# 04_LCD.net
KiCad netlist of a schematic drawn in Altium Designer
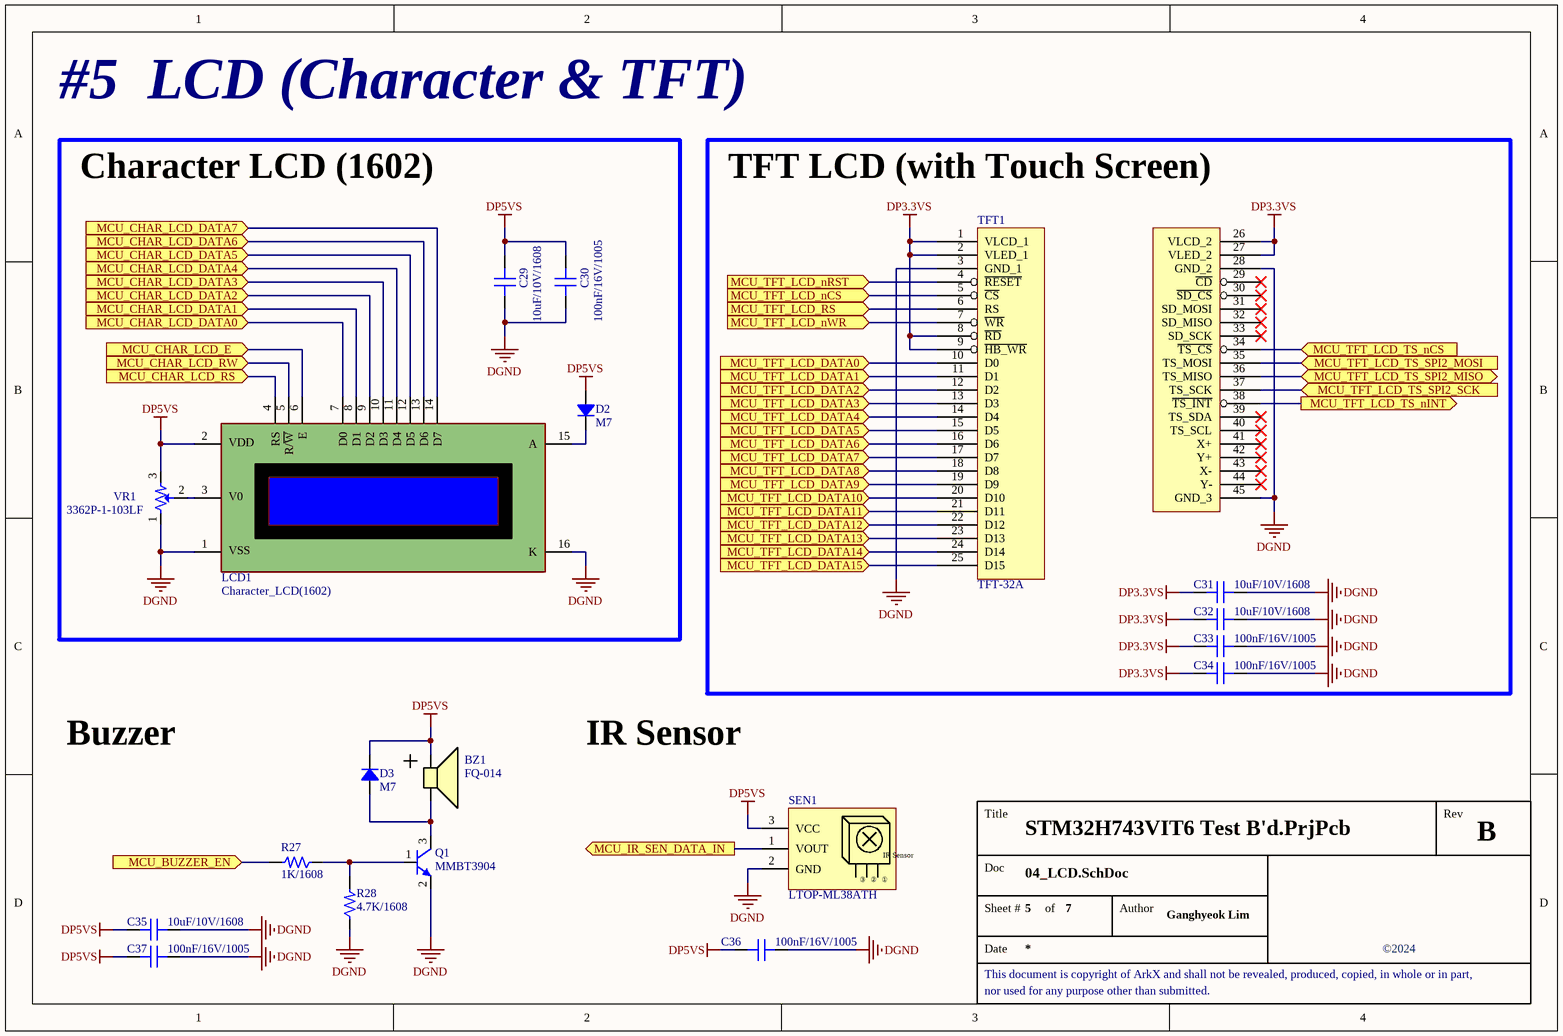
[diagram p0: 04_LCD.SchDoc]

(export (version "E")
  (design (tool "Eeschema 10.0.6"))
  (components
    (comp (ref "BZ1")
      (value "FQ-014")
      (footprint "BUZ FQ-013")
      (description "Magnetic Active Buzzer / Rated Voltage: 5V / Size: 9x5.5mm")
      (libsource (lib "Arkx") (part "BZ_FQ-014"))
    )
    (comp (ref "C29")
      (value "10uF/10V/1608")
      (footprint "CAP 1608 (0603_INCH)")
      (description "Ceramic CAP_10uF/10V/1608")
      (fields (field (name "LCSC PART #") "C19702"))
      (libsource (lib "Arkx") (part "CAP_10uF/10V/1608"))
    )
    (comp (ref "C30")
      (value "100nF/16V/1005")
      (footprint "CAP 1005 (0402_INCH)")
      (description "Ceramic CAP_100nF/16V/1005")
      (fields (field (name "LCSC PART #") "C1525"))
      (libsource (lib "Arkx") (part "CAP_100nF/16V/1005"))
    )
    (comp (ref "C31")
      (value "10uF/10V/1608")
      (footprint "CAP 1608 (0603_INCH)")
      (description "Ceramic CAP_10uF/10V/1608")
      (fields (field (name "LCSC PART #") "C19702"))
      (libsource (lib "Arkx") (part "CAP_10uF/10V/1608"))
    )
    (comp (ref "C32")
      (value "10uF/10V/1608")
      (footprint "CAP 1608 (0603_INCH)")
      (description "Ceramic CAP_10uF/10V/1608")
      (fields (field (name "LCSC PART #") "C19702"))
      (libsource (lib "Arkx") (part "CAP_10uF/10V/1608"))
    )
    (comp (ref "C33")
      (value "100nF/16V/1005")
      (footprint "CAP 1005 (0402_INCH)")
      (description "Ceramic CAP_100nF/16V/1005")
      (fields (field (name "LCSC PART #") "C1525"))
      (libsource (lib "Arkx") (part "CAP_100nF/16V/1005"))
    )
    (comp (ref "C34")
      (value "100nF/16V/1005")
      (footprint "CAP 1005 (0402_INCH)")
      (description "Ceramic CAP_100nF/16V/1005")
      (fields (field (name "LCSC PART #") "C1525"))
      (libsource (lib "Arkx") (part "CAP_100nF/16V/1005"))
    )
    (comp (ref "C35")
      (value "10uF/10V/1608")
      (footprint "CAP 1608 (0603_INCH)")
      (description "Ceramic CAP_10uF/10V/1608")
      (fields (field (name "LCSC PART #") "C19702"))
      (libsource (lib "Arkx") (part "CAP_10uF/10V/1608"))
    )
    (comp (ref "C36")
      (value "100nF/16V/1005")
      (footprint "CAP 1005 (0402_INCH)")
      (description "Ceramic CAP_100nF/16V/1005")
      (fields (field (name "LCSC PART #") "C1525"))
      (libsource (lib "Arkx") (part "CAP_100nF/16V/1005"))
    )
    (comp (ref "C37")
      (value "100nF/16V/1005")
      (footprint "CAP 1005 (0402_INCH)")
      (description "Ceramic CAP_100nF/16V/1005")
      (fields (field (name "LCSC PART #") "C1525"))
      (libsource (lib "Arkx") (part "CAP_100nF/16V/1005"))
    )
    (comp (ref "D2")
      (value "M7")
      (footprint "DIO DO-214AC (SMA)")
      (description "1A 5uA@1kV 1kV 1.1V@1A SMA(DO-214AC)  Diodes - General Purpose ROHS")
      (fields (field (name "LCSC PART #") "C95872"))
      (libsource (lib "Arkx") (part "DIO_M7"))
    )
    (comp (ref "D3")
      (value "M7")
      (footprint "DIO DO-214AC (SMA)")
      (description "1A 5uA@1kV 1kV 1.1V@1A SMA(DO-214AC)  Diodes - General Purpose ROHS")
      (fields (field (name "LCSC PART #") "C95872"))
      (libsource (lib "Arkx") (part "DIO_M7"))
    )
    (comp (ref "LCD1")
      (value "Character_LCD(1602)")
      (footprint "LCD_CHARACTOR-1602")
      (libsource (lib "Arkx") (part "LCD_Character-1602"))
    )
    (comp (ref "Q1")
      (value "MMBT3904")
      (footprint "SOT 23-3 (DIODES INCORPORATED)")
      (fields (field (name "LCSC PART #") "C20526"))
      (libsource (lib "Arkx") (part "BJT_NPN_MMBT3904"))
    )
    (comp (ref "R27")
      (value "1K/1608")
      (footprint "RES 1608 (0603_inch)")
      (description "RES_1K/1608/0.1W")
      (fields (field (name "LCSC PART #") "C21190"))
      (libsource (lib "Arkx") (part "RES_1K/1608/0.1W"))
    )
    (comp (ref "R28")
      (value "4.7K/1608")
      (footprint "RES 1608 (0603_inch)")
      (description "RES_4.7K/1608/0.1W")
      (fields (field (name "LCSC PART #") "C23162"))
      (libsource (lib "Arkx") (part "RES_4.7K/1608/0.1W"))
    )
    (comp (ref "SEN1")
      (value "LTOP-ML38ATH")
      (footprint "SEN_IR-LTOP-ML38ATH")
      (libsource (lib "Arkx") (part "SEN_IR_LTOP-ML38ATH"))
    )
    (comp (ref "TFT1")
      (value "TFT-32A")
      (footprint "LCD_TFT-32A")
      (libsource (lib "Arkx") (part "LCD_TFT-32A"))
    )
    (comp (ref "VR1")
      (value "3362P-1-103LF")
      (footprint "VR_3362P-1-103LF")
      (description "±10% ±100ppm/℃ 10kΩ Plugin  Variable Resistors/Potentiometers ROHS")
      (fields (field (name "LCSC PART #") "C58159"))
      (libsource (lib "Arkx") (part "VR_3362P-1-103LF"))
    )
  )
  (nets
    (net (code "1") (name "/MCU_BUZZER_EN") (class "Default")
      (node (ref "R27") (pin "2") (pinfunction "2_2") (pintype "passive"))
    )
    (net (code "2") (name "/MCU_CHAR_LCD_DATA0") (class "Default")
      (node (ref "LCD1") (pin "7") (pinfunction "D0_7") (pintype "passive"))
    )
    (net (code "3") (name "/MCU_CHAR_LCD_DATA1") (class "Default")
      (node (ref "LCD1") (pin "8") (pinfunction "D1_8") (pintype "passive"))
    )
    (net (code "4") (name "/MCU_CHAR_LCD_DATA2") (class "Default")
      (node (ref "LCD1") (pin "9") (pinfunction "D2_9") (pintype "passive"))
    )
    (net (code "5") (name "/MCU_CHAR_LCD_DATA3") (class "Default")
      (node (ref "LCD1") (pin "10") (pinfunction "D3_10") (pintype "passive"))
    )
    (net (code "6") (name "/MCU_CHAR_LCD_DATA4") (class "Default")
      (node (ref "LCD1") (pin "11") (pinfunction "D4_11") (pintype "passive"))
    )
    (net (code "7") (name "/MCU_CHAR_LCD_DATA5") (class "Default")
      (node (ref "LCD1") (pin "12") (pinfunction "D5_12") (pintype "passive"))
    )
    (net (code "8") (name "/MCU_CHAR_LCD_DATA6") (class "Default")
      (node (ref "LCD1") (pin "13") (pinfunction "D6_13") (pintype "passive"))
    )
    (net (code "9") (name "/MCU_CHAR_LCD_DATA7") (class "Default")
      (node (ref "LCD1") (pin "14") (pinfunction "D7_14") (pintype "passive"))
    )
    (net (code "10") (name "/MCU_CHAR_LCD_E") (class "Default")
      (node (ref "LCD1") (pin "6") (pinfunction "E_6") (pintype "passive"))
    )
    (net (code "11") (name "/MCU_CHAR_LCD_RS") (class "Default")
      (node (ref "LCD1") (pin "4") (pinfunction "RS_4") (pintype "passive"))
    )
    (net (code "12") (name "/MCU_CHAR_LCD_RW") (class "Default")
      (node (ref "LCD1") (pin "5") (pinfunction "R/~{W}_5") (pintype "passive"))
    )
    (net (code "13") (name "/MCU_IR_SEN_DATA_IN") (class "Default")
      (node (ref "SEN1") (pin "1") (pinfunction "VOUT_1") (pintype "passive"))
    )
    (net (code "14") (name "/MCU_TFT_LCD_DATA0") (class "Default")
      (node (ref "TFT1") (pin "10") (pinfunction "D0_10") (pintype "passive"))
    )
    (net (code "15") (name "/MCU_TFT_LCD_DATA1") (class "Default")
      (node (ref "TFT1") (pin "11") (pinfunction "D1_11") (pintype "passive"))
    )
    (net (code "16") (name "/MCU_TFT_LCD_DATA2") (class "Default")
      (node (ref "TFT1") (pin "12") (pinfunction "D2_12") (pintype "passive"))
    )
    (net (code "17") (name "/MCU_TFT_LCD_DATA3") (class "Default")
      (node (ref "TFT1") (pin "13") (pinfunction "D3_13") (pintype "passive"))
    )
    (net (code "18") (name "/MCU_TFT_LCD_DATA4") (class "Default")
      (node (ref "TFT1") (pin "14") (pinfunction "D4_14") (pintype "passive"))
    )
    (net (code "19") (name "/MCU_TFT_LCD_DATA5") (class "Default")
      (node (ref "TFT1") (pin "15") (pinfunction "D5_15") (pintype "passive"))
    )
    (net (code "20") (name "/MCU_TFT_LCD_DATA6") (class "Default")
      (node (ref "TFT1") (pin "16") (pinfunction "D6_16") (pintype "passive"))
    )
    (net (code "21") (name "/MCU_TFT_LCD_DATA7") (class "Default")
      (node (ref "TFT1") (pin "17") (pinfunction "D7_17") (pintype "passive"))
    )
    (net (code "22") (name "/MCU_TFT_LCD_DATA8") (class "Default")
      (node (ref "TFT1") (pin "18") (pinfunction "D8_18") (pintype "passive"))
    )
    (net (code "23") (name "/MCU_TFT_LCD_DATA9") (class "Default")
      (node (ref "TFT1") (pin "19") (pinfunction "D9_19") (pintype "passive"))
    )
    (net (code "24") (name "/MCU_TFT_LCD_DATA10") (class "Default")
      (node (ref "TFT1") (pin "20") (pinfunction "D10_20") (pintype "passive"))
    )
    (net (code "25") (name "/MCU_TFT_LCD_DATA11") (class "Default")
      (node (ref "TFT1") (pin "21") (pinfunction "D11_21") (pintype "passive"))
    )
    (net (code "26") (name "/MCU_TFT_LCD_DATA12") (class "Default")
      (node (ref "TFT1") (pin "22") (pinfunction "D12_22") (pintype "passive"))
    )
    (net (code "27") (name "/MCU_TFT_LCD_DATA13") (class "Default")
      (node (ref "TFT1") (pin "23") (pinfunction "D13_23") (pintype "passive"))
    )
    (net (code "28") (name "/MCU_TFT_LCD_DATA14") (class "Default")
      (node (ref "TFT1") (pin "24") (pinfunction "D14_24") (pintype "passive"))
    )
    (net (code "29") (name "/MCU_TFT_LCD_DATA15") (class "Default")
      (node (ref "TFT1") (pin "25") (pinfunction "D15_25") (pintype "passive"))
    )
    (net (code "30") (name "/MCU_TFT_LCD_RS") (class "Default")
      (node (ref "TFT1") (pin "6") (pinfunction "RS_6") (pintype "passive"))
    )
    (net (code "31") (name "/MCU_TFT_LCD_TS_SPI2_MISO") (class "Default")
      (node (ref "TFT1") (pin "36") (pinfunction "TS_MISO_36") (pintype "passive"))
    )
    (net (code "32") (name "/MCU_TFT_LCD_TS_SPI2_MOSI") (class "Default")
      (node (ref "TFT1") (pin "35") (pinfunction "TS_MOSI_35") (pintype "passive"))
    )
    (net (code "33") (name "/MCU_TFT_LCD_TS_SPI2_SCK") (class "Default")
      (node (ref "TFT1") (pin "37") (pinfunction "TS_SCK_37") (pintype "passive"))
    )
    (net (code "34") (name "/MCU_TFT_LCD_TS_nCS") (class "Default")
      (node (ref "TFT1") (pin "34") (pinfunction "~{TS_CS}_34") (pintype "passive"))
    )
    (net (code "35") (name "/MCU_TFT_LCD_TS_nINT") (class "Default")
      (node (ref "TFT1") (pin "38") (pinfunction "~{TS_INT}_38") (pintype "passive"))
    )
    (net (code "36") (name "/MCU_TFT_LCD_nCS") (class "Default")
      (node (ref "TFT1") (pin "5") (pinfunction "~{CS}_5") (pintype "passive"))
    )
    (net (code "37") (name "/MCU_TFT_LCD_nRST") (class "Default")
      (node (ref "TFT1") (pin "4") (pinfunction "~{RESET}_4") (pintype "passive"))
    )
    (net (code "38") (name "/MCU_TFT_LCD_nWR") (class "Default")
      (node (ref "TFT1") (pin "7") (pinfunction "~{WR}_7") (pintype "passive"))
    )
    (net (code "39") (name "DGND") (class "Default")
      (node (ref "C29") (pin "1") (pinfunction "1_1") (pintype "passive"))
      (node (ref "C30") (pin "1") (pinfunction "1_1") (pintype "passive"))
      (node (ref "C31") (pin "1") (pinfunction "1_1") (pintype "passive"))
      (node (ref "C32") (pin "1") (pinfunction "1_1") (pintype "passive"))
      (node (ref "C33") (pin "1") (pinfunction "1_1") (pintype "passive"))
      (node (ref "C34") (pin "1") (pinfunction "1_1") (pintype "passive"))
      (node (ref "C35") (pin "1") (pinfunction "1_1") (pintype "passive"))
      (node (ref "C36") (pin "1") (pinfunction "1_1") (pintype "passive"))
      (node (ref "C37") (pin "1") (pinfunction "1_1") (pintype "passive"))
      (node (ref "LCD1") (pin "1") (pinfunction "VSS_1") (pintype "passive"))
      (node (ref "LCD1") (pin "16") (pinfunction "K_16") (pintype "passive"))
      (node (ref "Q1") (pin "2") (pinfunction "E_2") (pintype "passive"))
      (node (ref "R28") (pin "1") (pinfunction "1_1") (pintype "passive"))
      (node (ref "SEN1") (pin "2") (pinfunction "GND_2") (pintype "passive"))
      (node (ref "TFT1") (pin "28") (pinfunction "GND_2_28") (pintype "power_in"))
      (node (ref "TFT1") (pin "3") (pinfunction "GND_1_3") (pintype "power_in"))
      (node (ref "TFT1") (pin "45") (pinfunction "GND_3_45") (pintype "power_in"))
      (node (ref "VR1") (pin "1") (pinfunction "1_1") (pintype "passive"))
    )
    (net (code "40") (name "DP3.3VS") (class "Default")
      (node (ref "C31") (pin "2") (pinfunction "2_2") (pintype "passive"))
      (node (ref "C32") (pin "2") (pinfunction "2_2") (pintype "passive"))
      (node (ref "C33") (pin "2") (pinfunction "2_2") (pintype "passive"))
      (node (ref "C34") (pin "2") (pinfunction "2_2") (pintype "passive"))
      (node (ref "TFT1") (pin "1") (pinfunction "VLCD_1_1") (pintype "power_in"))
      (node (ref "TFT1") (pin "2") (pinfunction "VLED_1_2") (pintype "power_in"))
      (node (ref "TFT1") (pin "26") (pinfunction "VLCD_2_26") (pintype "power_in"))
      (node (ref "TFT1") (pin "27") (pinfunction "VLED_2_27") (pintype "power_in"))
      (node (ref "TFT1") (pin "8") (pinfunction "~{RD}_8") (pintype "passive"))
      (node (ref "TFT1") (pin "9") (pinfunction "~{HB_WR}_9") (pintype "passive"))
    )
    (net (code "41") (name "DP5VS") (class "Default")
      (node (ref "BZ1") (pin "1") (pinfunction "1_1") (pintype "passive"))
      (node (ref "C29") (pin "2") (pinfunction "2_2") (pintype "passive"))
      (node (ref "C30") (pin "2") (pinfunction "2_2") (pintype "passive"))
      (node (ref "C35") (pin "2") (pinfunction "2_2") (pintype "passive"))
      (node (ref "C36") (pin "2") (pinfunction "2_2") (pintype "passive"))
      (node (ref "C37") (pin "2") (pinfunction "2_2") (pintype "passive"))
      (node (ref "D2") (pin "1") (pinfunction "1_1") (pintype "passive"))
      (node (ref "D3") (pin "2") (pinfunction "2_2") (pintype "passive"))
      (node (ref "LCD1") (pin "2") (pinfunction "VDD_2") (pintype "passive"))
      (node (ref "SEN1") (pin "3") (pinfunction "VCC_3") (pintype "passive"))
      (node (ref "VR1") (pin "3") (pinfunction "3_3") (pintype "passive"))
    )
    (net (code "42") (name "Net-(LCD1-A)") (class "Default")
      (node (ref "D2") (pin "2") (pinfunction "2_2") (pintype "passive"))
      (node (ref "LCD1") (pin "15") (pinfunction "A_15") (pintype "passive"))
    )
    (net (code "43") (name "Net-(LCD1-V0)") (class "Default")
      (node (ref "LCD1") (pin "3") (pinfunction "V0_3") (pintype "passive"))
      (node (ref "VR1") (pin "2") (pinfunction "2_2") (pintype "passive"))
    )
    (net (code "44") (name "Net-(Q1-B)") (class "Default")
      (node (ref "Q1") (pin "1") (pinfunction "B_1") (pintype "passive"))
      (node (ref "R27") (pin "1") (pinfunction "1_1") (pintype "passive"))
      (node (ref "R28") (pin "2") (pinfunction "2_2") (pintype "passive"))
    )
    (net (code "45") (name "Net-(Q1-C)") (class "Default")
      (node (ref "BZ1") (pin "2") (pinfunction "2_2") (pintype "passive"))
      (node (ref "D3") (pin "1") (pinfunction "1_1") (pintype "passive"))
      (node (ref "Q1") (pin "3") (pinfunction "C_3") (pintype "passive"))
    )
    (net (code "46") (name "unconnected-(TFT1-SD_MISO-Pad32)") (class "Default")
      (node (ref "TFT1") (pin "32") (pinfunction "SD_MISO_32") (pintype "passive+no_connect"))
    )
    (net (code "47") (name "unconnected-(TFT1-SD_MOSI-Pad31)") (class "Default")
      (node (ref "TFT1") (pin "31") (pinfunction "SD_MOSI_31") (pintype "passive+no_connect"))
    )
    (net (code "48") (name "unconnected-(TFT1-SD_SCK-Pad33)") (class "Default")
      (node (ref "TFT1") (pin "33") (pinfunction "SD_SCK_33") (pintype "passive+no_connect"))
    )
    (net (code "49") (name "unconnected-(TFT1-TS_SCL-Pad40)") (class "Default")
      (node (ref "TFT1") (pin "40") (pinfunction "TS_SCL_40") (pintype "passive+no_connect"))
    )
    (net (code "50") (name "unconnected-(TFT1-TS_SDA-Pad39)") (class "Default")
      (node (ref "TFT1") (pin "39") (pinfunction "TS_SDA_39") (pintype "passive+no_connect"))
    )
    (net (code "51") (name "unconnected-(TFT1-X+-Pad41)") (class "Default")
      (node (ref "TFT1") (pin "41") (pinfunction "X+_41") (pintype "passive+no_connect"))
    )
    (net (code "52") (name "unconnected-(TFT1-X--Pad43)") (class "Default")
      (node (ref "TFT1") (pin "43") (pinfunction "X-_43") (pintype "passive+no_connect"))
    )
    (net (code "53") (name "unconnected-(TFT1-Y+-Pad42)") (class "Default")
      (node (ref "TFT1") (pin "42") (pinfunction "Y+_42") (pintype "passive+no_connect"))
    )
    (net (code "54") (name "unconnected-(TFT1-Y--Pad44)") (class "Default")
      (node (ref "TFT1") (pin "44") (pinfunction "Y-_44") (pintype "passive+no_connect"))
    )
    (net (code "55") (name "unconnected-(TFT1-~{CD}-Pad29)") (class "Default")
      (node (ref "TFT1") (pin "29") (pinfunction "~{CD}_29") (pintype "passive+no_connect"))
    )
    (net (code "56") (name "unconnected-(TFT1-~{SD_CS}-Pad30)") (class "Default")
      (node (ref "TFT1") (pin "30") (pinfunction "~{SD_CS}_30") (pintype "passive+no_connect"))
    )
  )
)
